# Piksey_Nano_A1.net
KiCad netlist of a schematic drawn in EAGLE
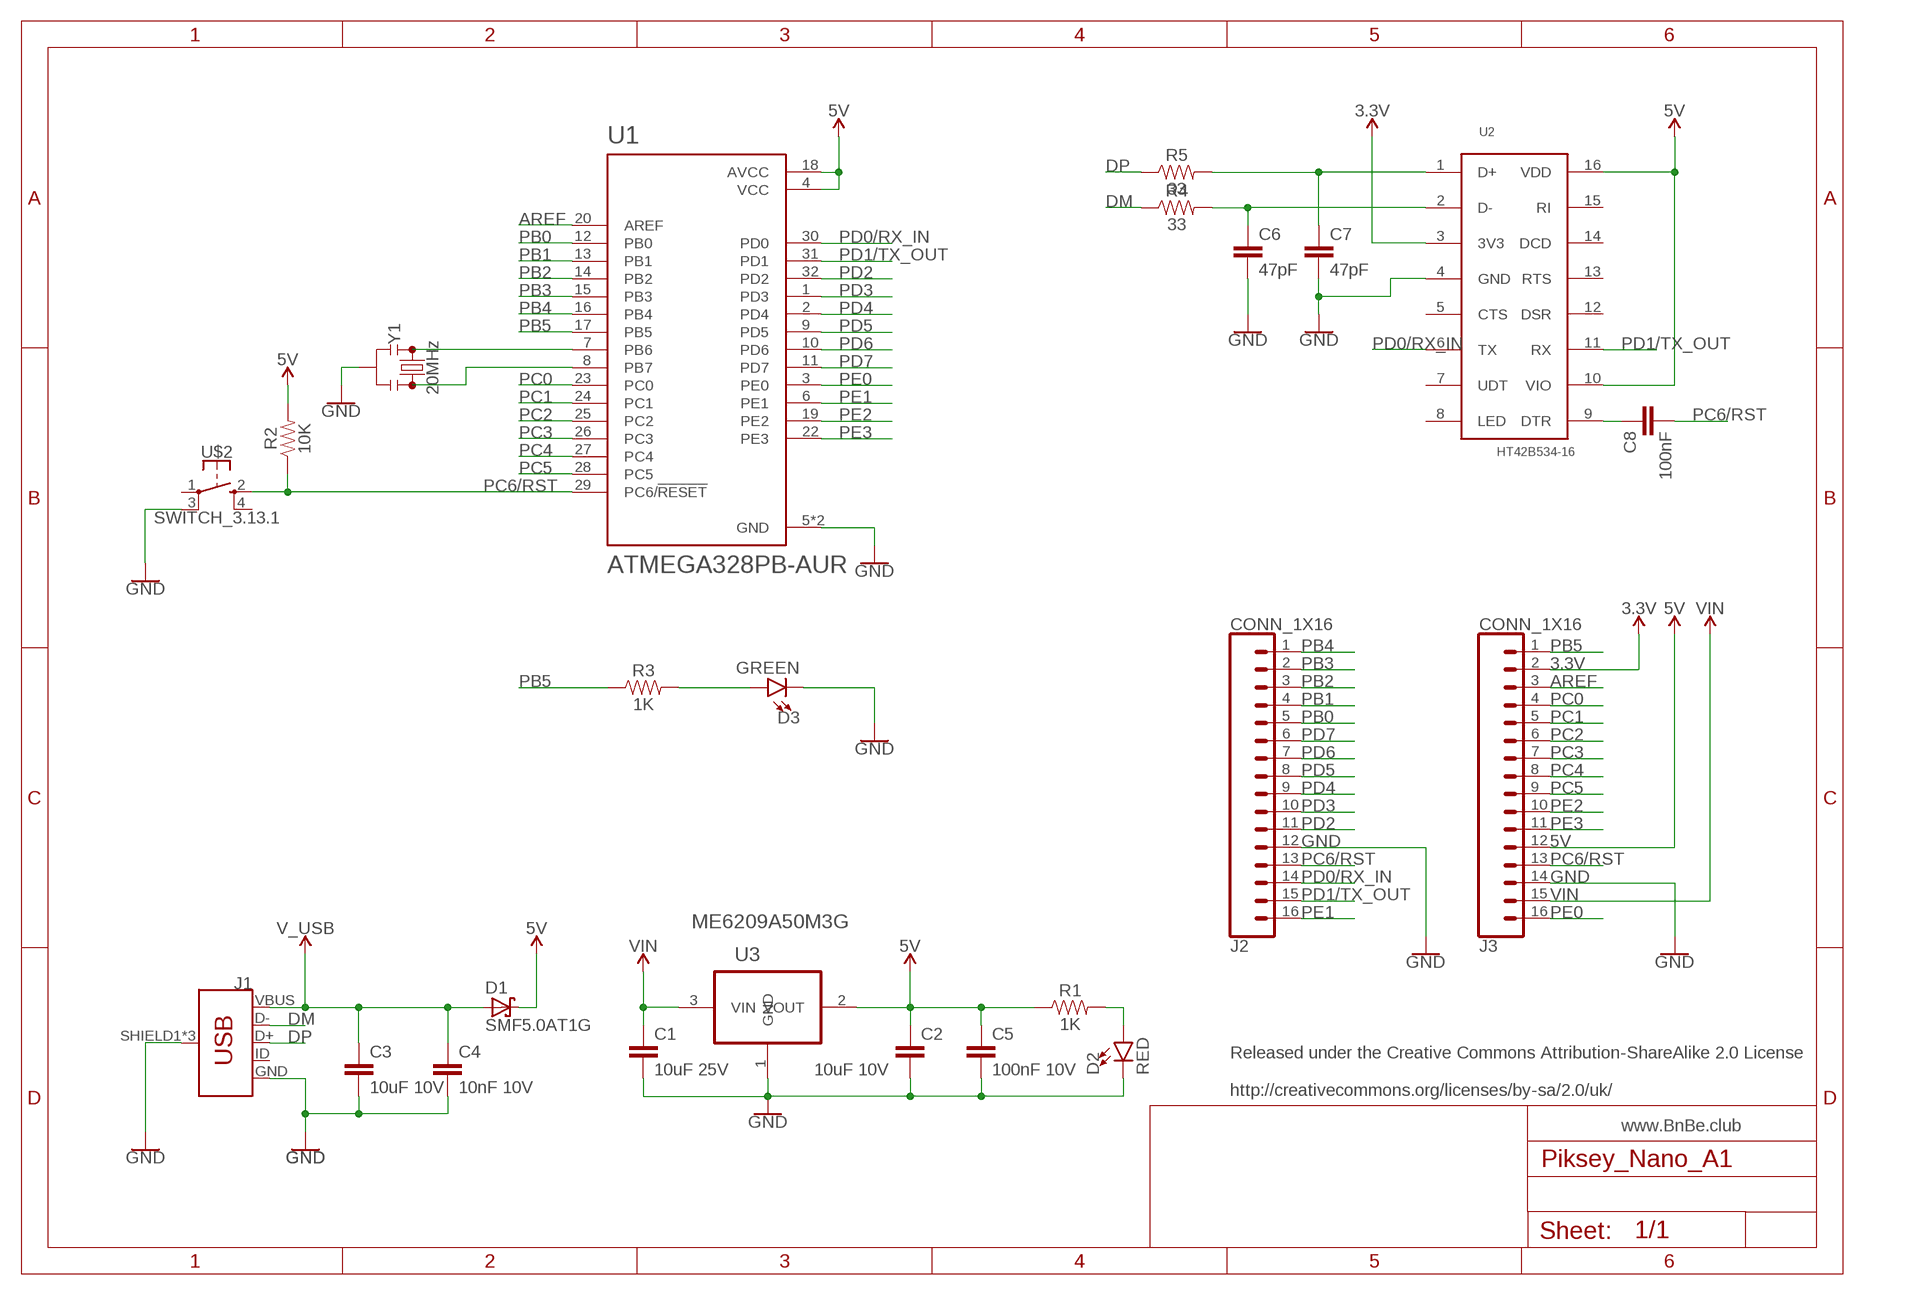
[diagram p0: schematic, sheet 1]

(export (version "E")
  (design (tool "Eeschema 10.0.6"))
  (components
    (comp (ref "C1")
      (value "10uF 25V")
      (footprint "eagle-import:0603")
      (libsource (lib "eagle-import") (part "10UF-0603-6.3V-20%"))
    )
    (comp (ref "C2")
      (value "10uF 10V")
      (footprint "eagle-import:0402")
      (libsource (lib "eagle-import") (part "100PF-0402-50V-5%"))
    )
    (comp (ref "C3")
      (value "10uF 10V")
      (footprint "eagle-import:0402")
      (libsource (lib "eagle-import") (part "100PF-0402-50V-5%"))
    )
    (comp (ref "C4")
      (value "10nF 10V")
      (footprint "eagle-import:0402")
      (libsource (lib "eagle-import") (part "100PF-0402-50V-5%"))
    )
    (comp (ref "C5")
      (value "100nF 10V")
      (footprint "eagle-import:0402")
      (libsource (lib "eagle-import") (part "100PF-0402-50V-5%"))
    )
    (comp (ref "C6")
      (value "47pF")
      (footprint "eagle-import:0402")
      (libsource (lib "eagle-import") (part "100PF-0402-50V-5%"))
    )
    (comp (ref "C7")
      (value "47pF")
      (footprint "eagle-import:0402")
      (libsource (lib "eagle-import") (part "100PF-0402-50V-5%"))
    )
    (comp (ref "C8")
      (value "100nF")
      (footprint "eagle-import:0402")
      (libsource (lib "eagle-import") (part "100PF-0402-50V-5%"))
    )
    (comp (ref "D1")
      (value "SMF5.0AT1G")
      (footprint "eagle-import:SOD123FL")
      (fields (field (name "MF") "Littelfuse"))
      (libsource (lib "eagle-import") (part "SMF5.0AT1G"))
    )
    (comp (ref "D2")
      (value "RED")
      (footprint "eagle-import:LED-0603")
      (libsource (lib "eagle-import") (part "LED0603"))
    )
    (comp (ref "D3")
      (value "GREEN")
      (footprint "eagle-import:LED-0603")
      (libsource (lib "eagle-import") (part "LED0603"))
    )
    (comp (ref "J1")
      (value "USB_MICRO-B_FEMALE-SMT")
      (footprint "eagle-import:USB-B-MICRO-SMD")
      (libsource (lib "eagle-import") (part "USB_MICRO-B_FEMALE-SMT"))
    )
    (comp (ref "J2")
      (value "CONN_1X16")
      (footprint "eagle-import:1X16")
      (libsource (lib "eagle-import") (part "CONN_1X16"))
    )
    (comp (ref "J3")
      (value "CONN_1X16")
      (footprint "eagle-import:1X16")
      (libsource (lib "eagle-import") (part "CONN_1X16"))
    )
    (comp (ref "R1")
      (value "1K")
      (footprint "eagle-import:0402")
      (libsource (lib "eagle-import") (part "RESISTOR0402"))
    )
    (comp (ref "R2")
      (value "10K")
      (footprint "eagle-import:0402")
      (libsource (lib "eagle-import") (part "RESISTOR0402"))
    )
    (comp (ref "R3")
      (value "1K")
      (footprint "eagle-import:0402")
      (libsource (lib "eagle-import") (part "RESISTOR0402"))
    )
    (comp (ref "R4")
      (value "33")
      (footprint "eagle-import:0402")
      (libsource (lib "eagle-import") (part "RESISTOR0402"))
    )
    (comp (ref "R5")
      (value "33")
      (footprint "eagle-import:0402")
      (libsource (lib "eagle-import") (part "RESISTOR0402"))
    )
    (comp (ref "U$2")
      (value "SWITCH_3.13.1")
      (footprint "eagle-import:SWITCH_3.1X3.1")
      (libsource (lib "eagle-import") (part "SWITCH_3.13.1"))
    )
    (comp (ref "U1")
      (value "ATMEGA328PB-AUR")
      (footprint "eagle-import:QFP80P900X900X120-32N")
      (fields (field (name "MF") "Microchip"))
      (libsource (lib "eagle-import") (part "ATMEGA328PB-AUR"))
    )
    (comp (ref "U2")
      (value "HT42B534-16")
      (footprint "eagle-import:NSOP-16")
      (libsource (lib "eagle-import") (part "HT42B534-16"))
    )
    (comp (ref "U3")
      (value "ME6209A50M3G")
      (footprint "eagle-import:SOT95P237X112-3N")
      (fields (field (name "MF") "Microchip") (field (name "MP") "MCP1700T-3302E/TT"))
      (libsource (lib "eagle-import") (part "MCP1700T-3302E/TT"))
    )
    (comp (ref "Y1")
      (value "20MHz")
      (footprint "eagle-import:RESONATOR-SMD-3.2X1.3")
      (libsource (lib "eagle-import") (part "RESONATOR-16MHZSMD_3.2X1.3"))
    )
  )
  (nets
    (net (code "1") (name "/AREF") (class "Default")
      (node (ref "J3") (pin "3") (pinfunction "3_3") (pintype "passive"))
      (node (ref "U1") (pin "20") (pinfunction "AREF_20") (pintype "input"))
    )
    (net (code "2") (name "/DM") (class "Default")
      (node (ref "J1") (pin "D-") (pinfunction "D-_D-") (pintype "bidirectional"))
      (node (ref "R4") (pin "1") (pinfunction "1_1") (pintype "passive"))
    )
    (net (code "3") (name "/DP") (class "Default")
      (node (ref "J1") (pin "D+") (pinfunction "D+_D+") (pintype "bidirectional"))
      (node (ref "R5") (pin "1") (pinfunction "1_1") (pintype "passive"))
    )
    (net (code "4") (name "/PB0") (class "Default")
      (node (ref "J2") (pin "5") (pinfunction "5_5") (pintype "passive"))
      (node (ref "U1") (pin "12") (pinfunction "PB0_12") (pintype "bidirectional"))
    )
    (net (code "5") (name "/PB1") (class "Default")
      (node (ref "J2") (pin "4") (pinfunction "4_4") (pintype "passive"))
      (node (ref "U1") (pin "13") (pinfunction "PB1_13") (pintype "bidirectional"))
    )
    (net (code "6") (name "/PB2") (class "Default")
      (node (ref "J2") (pin "3") (pinfunction "3_3") (pintype "passive"))
      (node (ref "U1") (pin "14") (pinfunction "PB2_14") (pintype "bidirectional"))
    )
    (net (code "7") (name "/PB3") (class "Default")
      (node (ref "J2") (pin "2") (pinfunction "2_2") (pintype "passive"))
      (node (ref "U1") (pin "15") (pinfunction "PB3_15") (pintype "bidirectional"))
    )
    (net (code "8") (name "/PB4") (class "Default")
      (node (ref "J2") (pin "1") (pinfunction "1_1") (pintype "passive"))
      (node (ref "U1") (pin "16") (pinfunction "PB4_16") (pintype "bidirectional"))
    )
    (net (code "9") (name "/PB5") (class "Default")
      (node (ref "J3") (pin "1") (pinfunction "1_1") (pintype "passive"))
      (node (ref "R3") (pin "1") (pinfunction "1_1") (pintype "passive"))
      (node (ref "U1") (pin "17") (pinfunction "PB5_17") (pintype "bidirectional"))
    )
    (net (code "10") (name "/PC0") (class "Default")
      (node (ref "J3") (pin "4") (pinfunction "4_4") (pintype "passive"))
      (node (ref "U1") (pin "23") (pinfunction "PC0_23") (pintype "bidirectional"))
    )
    (net (code "11") (name "/PC1") (class "Default")
      (node (ref "J3") (pin "5") (pinfunction "5_5") (pintype "passive"))
      (node (ref "U1") (pin "24") (pinfunction "PC1_24") (pintype "bidirectional"))
    )
    (net (code "12") (name "/PC2") (class "Default")
      (node (ref "J3") (pin "6") (pinfunction "6_6") (pintype "passive"))
      (node (ref "U1") (pin "25") (pinfunction "PC2_25") (pintype "bidirectional"))
    )
    (net (code "13") (name "/PC3") (class "Default")
      (node (ref "J3") (pin "7") (pinfunction "7_7") (pintype "passive"))
      (node (ref "U1") (pin "26") (pinfunction "PC3_26") (pintype "bidirectional"))
    )
    (net (code "14") (name "/PC4") (class "Default")
      (node (ref "J3") (pin "8") (pinfunction "8_8") (pintype "passive"))
      (node (ref "U1") (pin "27") (pinfunction "PC4_27") (pintype "bidirectional"))
    )
    (net (code "15") (name "/PC5") (class "Default")
      (node (ref "J3") (pin "9") (pinfunction "9_9") (pintype "passive"))
      (node (ref "U1") (pin "28") (pinfunction "PC5_28") (pintype "bidirectional"))
    )
    (net (code "16") (name "/PC6{slash}RST") (class "Default")
      (node (ref "C8") (pin "2") (pinfunction "2_2") (pintype "passive"))
      (node (ref "J2") (pin "13") (pinfunction "13_13") (pintype "passive"))
      (node (ref "J3") (pin "13") (pinfunction "13_13") (pintype "passive"))
      (node (ref "R2") (pin "1") (pinfunction "1_1") (pintype "passive"))
      (node (ref "U$2") (pin "2") (pinfunction "3_2") (pintype "passive"))
      (node (ref "U1") (pin "29") (pinfunction "PC6/~{RESET}_29") (pintype "bidirectional"))
    )
    (net (code "17") (name "/PD0{slash}RX_IN") (class "Default")
      (node (ref "J2") (pin "14") (pinfunction "14_14") (pintype "passive"))
      (node (ref "U1") (pin "30") (pinfunction "PD0_30") (pintype "bidirectional"))
      (node (ref "U2") (pin "6") (pinfunction "TX_6") (pintype "bidirectional"))
    )
    (net (code "18") (name "/PD1{slash}TX_OUT") (class "Default")
      (node (ref "J2") (pin "15") (pinfunction "15_15") (pintype "passive"))
      (node (ref "U1") (pin "31") (pinfunction "PD1_31") (pintype "bidirectional"))
      (node (ref "U2") (pin "11") (pinfunction "RX_11") (pintype "bidirectional"))
    )
    (net (code "19") (name "/PD2") (class "Default")
      (node (ref "J2") (pin "11") (pinfunction "11_11") (pintype "passive"))
      (node (ref "U1") (pin "32") (pinfunction "PD2_32") (pintype "bidirectional"))
    )
    (net (code "20") (name "/PD3") (class "Default")
      (node (ref "J2") (pin "10") (pinfunction "10_10") (pintype "passive"))
      (node (ref "U1") (pin "1") (pinfunction "PD3_1") (pintype "bidirectional"))
    )
    (net (code "21") (name "/PD4") (class "Default")
      (node (ref "J2") (pin "9") (pinfunction "9_9") (pintype "passive"))
      (node (ref "U1") (pin "2") (pinfunction "PD4_2") (pintype "bidirectional"))
    )
    (net (code "22") (name "/PD5") (class "Default")
      (node (ref "J2") (pin "8") (pinfunction "8_8") (pintype "passive"))
      (node (ref "U1") (pin "9") (pinfunction "PD5_9") (pintype "bidirectional"))
    )
    (net (code "23") (name "/PD6") (class "Default")
      (node (ref "J2") (pin "7") (pinfunction "7_7") (pintype "passive"))
      (node (ref "U1") (pin "10") (pinfunction "PD6_10") (pintype "bidirectional"))
    )
    (net (code "24") (name "/PD7") (class "Default")
      (node (ref "J2") (pin "6") (pinfunction "6_6") (pintype "passive"))
      (node (ref "U1") (pin "11") (pinfunction "PD7_11") (pintype "bidirectional"))
    )
    (net (code "25") (name "/PE0") (class "Default")
      (node (ref "J3") (pin "16") (pinfunction "16_16") (pintype "passive"))
      (node (ref "U1") (pin "3") (pinfunction "PE0_3") (pintype "bidirectional"))
    )
    (net (code "26") (name "/PE1") (class "Default")
      (node (ref "J2") (pin "16") (pinfunction "16_16") (pintype "passive"))
      (node (ref "U1") (pin "6") (pinfunction "PE1_6") (pintype "bidirectional"))
    )
    (net (code "27") (name "/PE2") (class "Default")
      (node (ref "J3") (pin "10") (pinfunction "10_10") (pintype "passive"))
      (node (ref "U1") (pin "19") (pinfunction "PE2_19") (pintype "bidirectional"))
    )
    (net (code "28") (name "/PE3") (class "Default")
      (node (ref "J3") (pin "11") (pinfunction "11_11") (pintype "passive"))
      (node (ref "U1") (pin "22") (pinfunction "PE3_22") (pintype "bidirectional"))
    )
    (net (code "29") (name "3.3V") (class "Default")
      (node (ref "J3") (pin "2") (pinfunction "2_2") (pintype "passive"))
      (node (ref "U2") (pin "3") (pinfunction "3V3_3") (pintype "bidirectional"))
    )
    (net (code "30") (name "5V") (class "Default")
      (node (ref "C2") (pin "1") (pinfunction "1_1") (pintype "passive"))
      (node (ref "C5") (pin "1") (pinfunction "1_1") (pintype "passive"))
      (node (ref "D1") (pin "C") (pinfunction "C_C") (pintype "passive"))
      (node (ref "J3") (pin "12") (pinfunction "12_12") (pintype "passive"))
      (node (ref "R1") (pin "1") (pinfunction "1_1") (pintype "passive"))
      (node (ref "R2") (pin "2") (pinfunction "2_2") (pintype "passive"))
      (node (ref "U1") (pin "18") (pinfunction "AVCC_18") (pintype "power_in"))
      (node (ref "U1") (pin "4") (pinfunction "VCC_4") (pintype "power_in"))
      (node (ref "U2") (pin "10") (pinfunction "VIO_10") (pintype "bidirectional"))
      (node (ref "U2") (pin "16") (pinfunction "VDD_16") (pintype "bidirectional"))
      (node (ref "U3") (pin "2") (pinfunction "VOUT_2") (pintype "output"))
    )
    (net (code "31") (name "GND") (class "Default")
      (node (ref "C1") (pin "2") (pinfunction "2_2") (pintype "passive"))
      (node (ref "C2") (pin "2") (pinfunction "2_2") (pintype "passive"))
      (node (ref "C3") (pin "2") (pinfunction "2_2") (pintype "passive"))
      (node (ref "C4") (pin "2") (pinfunction "2_2") (pintype "passive"))
      (node (ref "C5") (pin "2") (pinfunction "2_2") (pintype "passive"))
      (node (ref "C6") (pin "2") (pinfunction "2_2") (pintype "passive"))
      (node (ref "C7") (pin "2") (pinfunction "2_2") (pintype "passive"))
      (node (ref "D2") (pin "C") (pinfunction "C_C") (pintype "passive"))
      (node (ref "D3") (pin "C") (pinfunction "C_C") (pintype "passive"))
      (node (ref "J1") (pin "GND") (pinfunction "GND_GND") (pintype "power_in"))
      (node (ref "J1") (pin "SHIELD1") (pinfunction "SHIELD_SHIELD1") (pintype "bidirectional"))
      (node (ref "J1") (pin "SHIELD2") (pinfunction "SHIELD_SHIELD2") (pintype "bidirectional"))
      (node (ref "J1") (pin "SHIELD3") (pinfunction "SHIELD_SHIELD3") (pintype "bidirectional"))
      (node (ref "J2") (pin "12") (pinfunction "12_12") (pintype "passive"))
      (node (ref "J3") (pin "14") (pinfunction "14_14") (pintype "passive"))
      (node (ref "U$2") (pin "3") (pinfunction "2_3") (pintype "passive"))
      (node (ref "U1") (pin "21") (pinfunction "GND_21") (pintype "power_in"))
      (node (ref "U1") (pin "5") (pinfunction "GND_5") (pintype "power_in"))
      (node (ref "U2") (pin "4") (pinfunction "GND_4") (pintype "bidirectional"))
      (node (ref "U3") (pin "1") (pinfunction "GND_1") (pintype "passive"))
      (node (ref "Y1") (pin "2") (pinfunction "2_2") (pintype "passive"))
    )
    (net (code "32") (name "Net-(D2-PadA)") (class "Default")
      (node (ref "D2") (pin "A") (pinfunction "A_A") (pintype "passive"))
      (node (ref "R1") (pin "2") (pinfunction "2_2") (pintype "passive"))
    )
    (net (code "33") (name "Net-(D3-PadA)") (class "Default")
      (node (ref "D3") (pin "A") (pinfunction "A_A") (pintype "passive"))
      (node (ref "R3") (pin "2") (pinfunction "2_2") (pintype "passive"))
    )
    (net (code "34") (name "Net-(U1-PB6)") (class "Default")
      (node (ref "U1") (pin "7") (pinfunction "PB6_7") (pintype "bidirectional"))
      (node (ref "Y1") (pin "1") (pinfunction "1_1") (pintype "passive"))
    )
    (net (code "35") (name "Net-(U1-PB7)") (class "Default")
      (node (ref "U1") (pin "8") (pinfunction "PB7_8") (pintype "bidirectional"))
      (node (ref "Y1") (pin "3") (pinfunction "3_3") (pintype "passive"))
    )
    (net (code "36") (name "Net-(U2-D+)") (class "Default")
      (node (ref "C7") (pin "1") (pinfunction "1_1") (pintype "passive"))
      (node (ref "R5") (pin "2") (pinfunction "2_2") (pintype "passive"))
      (node (ref "U2") (pin "1") (pinfunction "D+_1") (pintype "bidirectional"))
    )
    (net (code "37") (name "Net-(U2-D-)") (class "Default")
      (node (ref "C6") (pin "1") (pinfunction "1_1") (pintype "passive"))
      (node (ref "R4") (pin "2") (pinfunction "2_2") (pintype "passive"))
      (node (ref "U2") (pin "2") (pinfunction "D-_2") (pintype "bidirectional"))
    )
    (net (code "38") (name "Net-(U2-DTR)") (class "Default")
      (node (ref "C8") (pin "1") (pinfunction "1_1") (pintype "passive"))
      (node (ref "U2") (pin "9") (pinfunction "DTR_9") (pintype "bidirectional"))
    )
    (net (code "39") (name "VIN") (class "Default")
      (node (ref "C1") (pin "1") (pinfunction "1_1") (pintype "passive"))
      (node (ref "J3") (pin "15") (pinfunction "15_15") (pintype "passive"))
      (node (ref "U3") (pin "3") (pinfunction "VIN_3") (pintype "input"))
    )
    (net (code "40") (name "V_USB") (class "Default")
      (node (ref "C3") (pin "1") (pinfunction "1_1") (pintype "passive"))
      (node (ref "C4") (pin "1") (pinfunction "1_1") (pintype "passive"))
      (node (ref "D1") (pin "A") (pinfunction "A_A") (pintype "passive"))
      (node (ref "J1") (pin "VBUS") (pinfunction "VBUS_VBUS") (pintype "power_in"))
    )
    (net (code "41") (name "unconnected-(J1-PadID)") (class "Default")
      (node (ref "J1") (pin "ID") (pinfunction "ID_ID") (pintype "bidirectional"))
    )
    (net (code "42") (name "unconnected-(U$2-Pad1)") (class "Default")
      (node (ref "U$2") (pin "1") (pinfunction "1_1") (pintype "passive"))
    )
    (net (code "43") (name "unconnected-(U$2-Pad4)") (class "Default")
      (node (ref "U$2") (pin "4") (pinfunction "4_4") (pintype "passive"))
    )
    (net (code "44") (name "unconnected-(U2-CTS-Pad5)") (class "Default")
      (node (ref "U2") (pin "5") (pinfunction "CTS_5") (pintype "bidirectional"))
    )
    (net (code "45") (name "unconnected-(U2-DCD-Pad14)") (class "Default")
      (node (ref "U2") (pin "14") (pinfunction "DCD_14") (pintype "bidirectional"))
    )
    (net (code "46") (name "unconnected-(U2-DSR-Pad12)") (class "Default")
      (node (ref "U2") (pin "12") (pinfunction "DSR_12") (pintype "bidirectional"))
    )
    (net (code "47") (name "unconnected-(U2-LED-Pad8)") (class "Default")
      (node (ref "U2") (pin "8") (pinfunction "LED_8") (pintype "bidirectional"))
    )
    (net (code "48") (name "unconnected-(U2-RI-Pad15)") (class "Default")
      (node (ref "U2") (pin "15") (pinfunction "RI_15") (pintype "bidirectional"))
    )
    (net (code "49") (name "unconnected-(U2-RTS-Pad13)") (class "Default")
      (node (ref "U2") (pin "13") (pinfunction "RTS_13") (pintype "bidirectional"))
    )
    (net (code "50") (name "unconnected-(U2-UDT-Pad7)") (class "Default")
      (node (ref "U2") (pin "7") (pinfunction "UDT_7") (pintype "bidirectional"))
    )
  )
)
